# SchemaC.net
KiCad netlist of a schematic drawn in Altium Designer
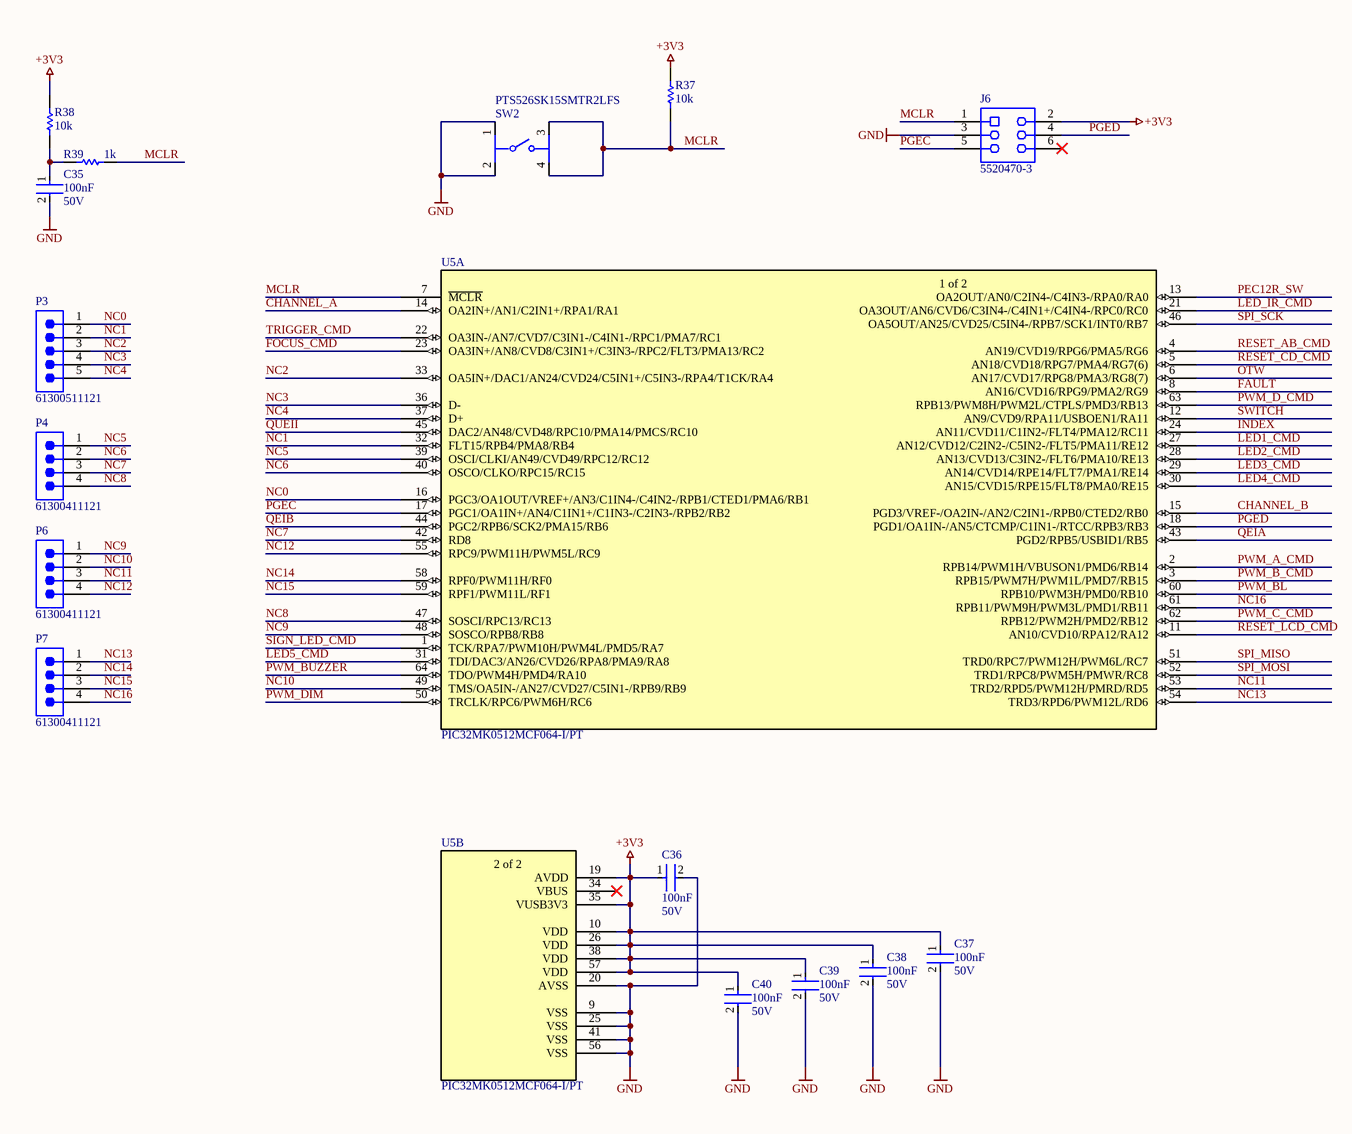
[diagram p0: SchemaC.SchDoc]

(export (version "E")
  (design (tool "Eeschema 10.0.6"))
  (components
    (comp (ref "C35")
      (value "CL21B104KBCNNNC")
      (footprint "FP-CL21-IPC_C")
      (description "CL21 Series 0805 100nF 50V ±10% Tolerance X7R Multilayer Ceramic Chip Capacitor")
      (fields
        (field (name "TOLERANCE") "10%")
        (field (name "CAPACITANCE") "100nF")
        (field (name "VOLTAGE RATING") "50V")
        (field (name "VOLTAGE") "50V")
      )
      (libsource (lib "Altium Content Vault") (part "b4654b650e69147ec39a6b967a45e02"))
    )
    (comp (ref "C36")
      (value "CL21B104KBCNNNC")
      (footprint "FP-CL21-IPC_C")
      (description "CL21 Series 0805 100nF 50V ±10% Tolerance X7R Multilayer Ceramic Chip Capacitor")
      (fields
        (field (name "TOLERANCE") "10%")
        (field (name "CAPACITANCE") "100nF")
        (field (name "VOLTAGE RATING") "50V")
        (field (name "VOLTAGE") "50V")
      )
      (libsource (lib "Altium Content Vault") (part "b4654b650e69147ec39a6b967a45e02"))
    )
    (comp (ref "C37")
      (value "CL21B104KBCNNNC")
      (footprint "FP-CL21-IPC_C")
      (description "CL21 Series 0805 100nF 50V ±10% Tolerance X7R Multilayer Ceramic Chip Capacitor")
      (fields
        (field (name "TOLERANCE") "10%")
        (field (name "CAPACITANCE") "100nF")
        (field (name "VOLTAGE RATING") "50V")
        (field (name "VOLTAGE") "50V")
      )
      (libsource (lib "Altium Content Vault") (part "b4654b650e69147ec39a6b967a45e02"))
    )
    (comp (ref "C38")
      (value "CL21B104KBCNNNC")
      (footprint "FP-CL21-IPC_C")
      (description "CL21 Series 0805 100nF 50V ±10% Tolerance X7R Multilayer Ceramic Chip Capacitor")
      (fields
        (field (name "TOLERANCE") "10%")
        (field (name "CAPACITANCE") "100nF")
        (field (name "VOLTAGE RATING") "50V")
        (field (name "VOLTAGE") "50V")
      )
      (libsource (lib "Altium Content Vault") (part "b4654b650e69147ec39a6b967a45e02"))
    )
    (comp (ref "C39")
      (value "CL21B104KBCNNNC")
      (footprint "FP-CL21-IPC_C")
      (description "CL21 Series 0805 100nF 50V ±10% Tolerance X7R Multilayer Ceramic Chip Capacitor")
      (fields
        (field (name "TOLERANCE") "10%")
        (field (name "CAPACITANCE") "100nF")
        (field (name "VOLTAGE RATING") "50V")
        (field (name "VOLTAGE") "50V")
      )
      (libsource (lib "Altium Content Vault") (part "b4654b650e69147ec39a6b967a45e02"))
    )
    (comp (ref "C40")
      (value "CL21B104KBCNNNC")
      (footprint "FP-CL21-IPC_C")
      (description "CL21 Series 0805 100nF 50V ±10% Tolerance X7R Multilayer Ceramic Chip Capacitor")
      (fields
        (field (name "TOLERANCE") "10%")
        (field (name "CAPACITANCE") "100nF")
        (field (name "VOLTAGE RATING") "50V")
        (field (name "VOLTAGE") "50V")
      )
      (libsource (lib "Altium Content Vault") (part "b4654b650e69147ec39a6b967a45e02"))
    )
    (comp (ref "J6")
      (value "5520470-3")
      (footprint "TECO-5520470-3_V")
      (description "Modular Jack, 6 Position, Right Angle, RoHS, Tray")
      (fields (field (name "MANUFACTURER") "TE Connectivity"))
      (libsource (lib "Altium Content Vault") (part "CN-2S-F-R6"))
    )
    (comp (ref "P3")
      (value "61300511121")
      (footprint "61300511121")
      (libsource (lib "Altium Content Vault") (part "Header_Male_1R_05P"))
    )
    (comp (ref "P4")
      (value "61300411121")
      (footprint "61300411121")
      (libsource (lib "Altium Content Vault") (part "Header_Male_1R_04P"))
    )
    (comp (ref "P6")
      (value "61300411121")
      (footprint "61300411121")
      (libsource (lib "Altium Content Vault") (part "Header_Male_1R_04P"))
    )
    (comp (ref "P7")
      (value "61300411121")
      (footprint "61300411121")
      (libsource (lib "Altium Content Vault") (part "Header_Male_1R_04P"))
    )
    (comp (ref "R37")
      (value "RC0805JR-0710KL")
      (footprint "RESC2013X60X35ML10T20")
      (description "Chip Resistor, 10 KOhm, +/- 5%, 0.125 W, -55 to 155 degC, 0805 (2012 Metric), RoHS, Tape and Reel")
      (fields (field (name "MANUFACTURER") "Yageo") (field (name "RESISTANCE") "10k"))
      (libsource (lib "Altium Content Vault") (part "RES-2"))
    )
    (comp (ref "R38")
      (value "RC0805JR-0710KL")
      (footprint "RESC2013X60X35ML10T20")
      (description "Chip Resistor, 10 KOhm, +/- 5%, 0.125 W, -55 to 155 degC, 0805 (2012 Metric), RoHS, Tape and Reel")
      (fields (field (name "MANUFACTURER") "Yageo") (field (name "RESISTANCE") "10k"))
      (libsource (lib "Altium Content Vault") (part "RES-2"))
    )
    (comp (ref "R39")
      (value "RC0805FR-071KL")
      (footprint "RESC2013X60X35ML10T20")
      (description "Chip Resistor, 1 KOhm, +/- 1%, 125 mW, -55 to 155 degC, 0805 (2012 Metric), RoHS, Tape and Reel")
      (fields
        (field (name "RESISTANCE") "1k")
        (field (name "TOLERANCE") "1%")
        (field (name "MANUFACTURER") "Yageo")
      )
      (libsource (lib "Altium Content Vault") (part "RES-2"))
    )
    (comp (ref "SW2")
      (value "PTS526SK15SMTR2LFS")
      (footprint "FP-PTS526SK15SMTR2LFS-MFG")
      (description "Tactile Switch SPST-NO Top Actuated Surface Mount")
      (fields (field (name "MANUFACTURER") "C&K"))
      (libsource (lib "Altium Content Vault") (part "b8895f3f4cefb76e1819d2863dba89b"))
    )
    (comp (ref "U5")
      (value "PIC32MK0512MCF064-I/PT")
      (footprint "TQFP64_PT_MCH")
      (fields (field (name "COPYRIGHT") "Copyright (C) 2023 Ultra Librarian. All rights reserved."))
      (libsource (lib "SymbLib") (part "PIC32MK0512MCF064-I/PT"))
    )
  )
  (nets
    (net (code "1") (name "+3V3") (class "Default")
      (node (ref "C36") (pin "1") (pinfunction "1_1") (pintype "passive"))
      (node (ref "C37") (pin "1") (pinfunction "1_1") (pintype "passive"))
      (node (ref "C38") (pin "1") (pinfunction "1_1") (pintype "passive"))
      (node (ref "C39") (pin "1") (pinfunction "1_1") (pintype "passive"))
      (node (ref "C40") (pin "1") (pinfunction "1_1") (pintype "passive"))
      (node (ref "J6") (pin "2") (pinfunction "2_2") (pintype "passive"))
      (node (ref "R37") (pin "2") (pinfunction "2_2") (pintype "passive"))
      (node (ref "R38") (pin "2") (pinfunction "2_2") (pintype "passive"))
      (node (ref "U5") (pin "10") (pinfunction "VDD_10") (pintype "power_in"))
      (node (ref "U5") (pin "19") (pinfunction "AVDD_19") (pintype "power_in"))
      (node (ref "U5") (pin "26") (pinfunction "VDD_26") (pintype "power_in"))
      (node (ref "U5") (pin "35") (pinfunction "VUSB3V3_35") (pintype "power_in"))
      (node (ref "U5") (pin "38") (pinfunction "VDD_38") (pintype "power_in"))
      (node (ref "U5") (pin "57") (pinfunction "VDD_57") (pintype "power_in"))
    )
    (net (code "2") (name "/CHANNEL_A") (class "Default")
      (node (ref "U5") (pin "14") (pinfunction "OA2IN+/AN1/C2IN1+/RPA1/RA1_14") (pintype "bidirectional"))
    )
    (net (code "3") (name "/CHANNEL_B") (class "Default")
      (node (ref "U5") (pin "15") (pinfunction "PGD3/VREF-/OA2IN-/AN2/C2IN1-/RPB0/CTED2/RB0_15") (pintype "bidirectional"))
    )
    (net (code "4") (name "/FAULT") (class "Default")
      (node (ref "U5") (pin "8") (pinfunction "AN16/CVD16/RPG9/PMA2/RG9_8") (pintype "bidirectional"))
    )
    (net (code "5") (name "/FOCUS_CMD") (class "Default")
      (node (ref "U5") (pin "23") (pinfunction "OA3IN+/AN8/CVD8/C3IN1+/C3IN3-/RPC2/FLT3/PMA13/RC2_23") (pintype "bidirectional"))
    )
    (net (code "6") (name "/INDEX") (class "Default")
      (node (ref "U5") (pin "24") (pinfunction "AN11/CVD11/C1IN2-/FLT4/PMA12/RC11_24") (pintype "bidirectional"))
    )
    (net (code "7") (name "/LED1_CMD") (class "Default")
      (node (ref "U5") (pin "27") (pinfunction "AN12/CVD12/C2IN2-/C5IN2-/FLT5/PMA11/RE12_27") (pintype "bidirectional"))
    )
    (net (code "8") (name "/LED2_CMD") (class "Default")
      (node (ref "U5") (pin "28") (pinfunction "AN13/CVD13/C3IN2-/FLT6/PMA10/RE13_28") (pintype "bidirectional"))
    )
    (net (code "9") (name "/LED3_CMD") (class "Default")
      (node (ref "U5") (pin "29") (pinfunction "AN14/CVD14/RPE14/FLT7/PMA1/RE14_29") (pintype "bidirectional"))
    )
    (net (code "10") (name "/LED4_CMD") (class "Default")
      (node (ref "U5") (pin "30") (pinfunction "AN15/CVD15/RPE15/FLT8/PMA0/RE15_30") (pintype "bidirectional"))
    )
    (net (code "11") (name "/LED5_CMD") (class "Default")
      (node (ref "U5") (pin "31") (pinfunction "TDI/DAC3/AN26/CVD26/RPA8/PMA9/RA8_31") (pintype "bidirectional"))
    )
    (net (code "12") (name "/LED_IR_CMD") (class "Default")
      (node (ref "U5") (pin "21") (pinfunction "OA3OUT/AN6/CVD6/C3IN4-/C4IN1+/C4IN4-/RPC0/RC0_21") (pintype "bidirectional"))
    )
    (net (code "13") (name "/MCLR") (class "Default")
      (node (ref "J6") (pin "1") (pinfunction "1_1") (pintype "passive"))
      (node (ref "R37") (pin "1") (pinfunction "1_1") (pintype "passive"))
      (node (ref "R39") (pin "2") (pinfunction "2_2") (pintype "passive"))
      (node (ref "SW2") (pin "3") (pinfunction "3_3") (pintype "passive"))
      (node (ref "SW2") (pin "4") (pinfunction "4_4") (pintype "passive"))
      (node (ref "U5") (pin "7") (pinfunction "~{MCLR}_7") (pintype "passive"))
    )
    (net (code "14") (name "/NC0") (class "Default")
      (node (ref "P3") (pin "1") (pinfunction "1_1") (pintype "passive"))
      (node (ref "U5") (pin "16") (pinfunction "PGC3/OA1OUT/VREF+/AN3/C1IN4-/C4IN2-/RPB1/CTED1/PMA6/RB1_16") (pintype "bidirectional"))
    )
    (net (code "15") (name "/NC1") (class "Default")
      (node (ref "P3") (pin "2") (pinfunction "2_2") (pintype "passive"))
      (node (ref "U5") (pin "32") (pinfunction "FLT15/RPB4/PMA8/RB4_32") (pintype "bidirectional"))
    )
    (net (code "16") (name "/NC2") (class "Default")
      (node (ref "P3") (pin "3") (pinfunction "3_3") (pintype "passive"))
      (node (ref "U5") (pin "33") (pinfunction "OA5IN+/DAC1/AN24/CVD24/C5IN1+/C5IN3-/RPA4/T1CK/RA4_33") (pintype "bidirectional"))
    )
    (net (code "17") (name "/NC3") (class "Default")
      (node (ref "P3") (pin "4") (pinfunction "4_4") (pintype "passive"))
      (node (ref "U5") (pin "36") (pinfunction "D-_36") (pintype "bidirectional"))
    )
    (net (code "18") (name "/NC4") (class "Default")
      (node (ref "P3") (pin "5") (pinfunction "5_5") (pintype "passive"))
      (node (ref "U5") (pin "37") (pinfunction "D+_37") (pintype "bidirectional"))
    )
    (net (code "19") (name "/NC5") (class "Default")
      (node (ref "P4") (pin "1") (pinfunction "1_1") (pintype "passive"))
      (node (ref "U5") (pin "39") (pinfunction "OSCI/CLKI/AN49/CVD49/RPC12/RC12_39") (pintype "bidirectional"))
    )
    (net (code "20") (name "/NC6") (class "Default")
      (node (ref "P4") (pin "2") (pinfunction "2_2") (pintype "passive"))
      (node (ref "U5") (pin "40") (pinfunction "OSCO/CLKO/RPC15/RC15_40") (pintype "bidirectional"))
    )
    (net (code "21") (name "/NC7") (class "Default")
      (node (ref "P4") (pin "3") (pinfunction "3_3") (pintype "passive"))
      (node (ref "U5") (pin "42") (pinfunction "RD8_42") (pintype "bidirectional"))
    )
    (net (code "22") (name "/NC8") (class "Default")
      (node (ref "P4") (pin "4") (pinfunction "4_4") (pintype "passive"))
      (node (ref "U5") (pin "47") (pinfunction "SOSCI/RPC13/RC13_47") (pintype "bidirectional"))
    )
    (net (code "23") (name "/NC9") (class "Default")
      (node (ref "P6") (pin "1") (pinfunction "1_1") (pintype "passive"))
      (node (ref "U5") (pin "48") (pinfunction "SOSCO/RPB8/RB8_48") (pintype "bidirectional"))
    )
    (net (code "24") (name "/NC10") (class "Default")
      (node (ref "P6") (pin "2") (pinfunction "2_2") (pintype "passive"))
      (node (ref "U5") (pin "49") (pinfunction "TMS/OA5IN-/AN27/CVD27/C5IN1-/RPB9/RB9_49") (pintype "bidirectional"))
    )
    (net (code "25") (name "/NC11") (class "Default")
      (node (ref "P6") (pin "3") (pinfunction "3_3") (pintype "passive"))
      (node (ref "U5") (pin "53") (pinfunction "TRD2/RPD5/PWM12H/PMRD/RD5_53") (pintype "bidirectional"))
    )
    (net (code "26") (name "/NC12") (class "Default")
      (node (ref "P6") (pin "4") (pinfunction "4_4") (pintype "passive"))
      (node (ref "U5") (pin "55") (pinfunction "RPC9/PWM11H/PWM5L/RC9_55") (pintype "bidirectional"))
    )
    (net (code "27") (name "/NC13") (class "Default")
      (node (ref "P7") (pin "1") (pinfunction "1_1") (pintype "passive"))
      (node (ref "U5") (pin "54") (pinfunction "TRD3/RPD6/PWM12L/RD6_54") (pintype "bidirectional"))
    )
    (net (code "28") (name "/NC14") (class "Default")
      (node (ref "P7") (pin "2") (pinfunction "2_2") (pintype "passive"))
      (node (ref "U5") (pin "58") (pinfunction "RPF0/PWM11H/RF0_58") (pintype "bidirectional"))
    )
    (net (code "29") (name "/NC15") (class "Default")
      (node (ref "P7") (pin "3") (pinfunction "3_3") (pintype "passive"))
      (node (ref "U5") (pin "59") (pinfunction "RPF1/PWM11L/RF1_59") (pintype "bidirectional"))
    )
    (net (code "30") (name "/NC16") (class "Default")
      (node (ref "P7") (pin "4") (pinfunction "4_4") (pintype "passive"))
      (node (ref "U5") (pin "61") (pinfunction "RPB11/PWM9H/PWM3L/PMD1/RB11_61") (pintype "bidirectional"))
    )
    (net (code "31") (name "/OTW") (class "Default")
      (node (ref "U5") (pin "6") (pinfunction "AN17/CVD17/RPG8/PMA3/RG8(7)_6") (pintype "bidirectional"))
    )
    (net (code "32") (name "/PEC12R_SW") (class "Default")
      (node (ref "U5") (pin "13") (pinfunction "OA2OUT/AN0/C2IN4-/C4IN3-/RPA0/RA0_13") (pintype "bidirectional"))
    )
    (net (code "33") (name "/PGEC") (class "Default")
      (node (ref "J6") (pin "5") (pinfunction "5_5") (pintype "passive"))
      (node (ref "U5") (pin "17") (pinfunction "PGC1/OA1IN+/AN4/C1IN1+/C1IN3-/C2IN3-/RPB2/RB2_17") (pintype "bidirectional"))
    )
    (net (code "34") (name "/PGED") (class "Default")
      (node (ref "J6") (pin "4") (pinfunction "4_4") (pintype "passive"))
      (node (ref "U5") (pin "18") (pinfunction "PGD1/OA1IN-/AN5/CTCMP/C1IN1-/RTCC/RPB3/RB3_18") (pintype "bidirectional"))
    )
    (net (code "35") (name "/PWM_A_CMD") (class "Default")
      (node (ref "U5") (pin "2") (pinfunction "RPB14/PWM1H/VBUSON1/PMD6/RB14_2") (pintype "bidirectional"))
    )
    (net (code "36") (name "/PWM_BL") (class "Default")
      (node (ref "U5") (pin "60") (pinfunction "RPB10/PWM3H/PMD0/RB10_60") (pintype "bidirectional"))
    )
    (net (code "37") (name "/PWM_BUZZER") (class "Default")
      (node (ref "U5") (pin "64") (pinfunction "TDO/PWM4H/PMD4/RA10_64") (pintype "bidirectional"))
    )
    (net (code "38") (name "/PWM_B_CMD") (class "Default")
      (node (ref "U5") (pin "3") (pinfunction "RPB15/PWM7H/PWM1L/PMD7/RB15_3") (pintype "bidirectional"))
    )
    (net (code "39") (name "/PWM_C_CMD") (class "Default")
      (node (ref "U5") (pin "62") (pinfunction "RPB12/PWM2H/PMD2/RB12_62") (pintype "bidirectional"))
    )
    (net (code "40") (name "/PWM_DIM") (class "Default")
      (node (ref "U5") (pin "50") (pinfunction "TRCLK/RPC6/PWM6H/RC6_50") (pintype "bidirectional"))
    )
    (net (code "41") (name "/PWM_D_CMD") (class "Default")
      (node (ref "U5") (pin "63") (pinfunction "RPB13/PWM8H/PWM2L/CTPLS/PMD3/RB13_63") (pintype "bidirectional"))
    )
    (net (code "42") (name "/QEIA") (class "Default")
      (node (ref "U5") (pin "43") (pinfunction "PGD2/RPB5/USBID1/RB5_43") (pintype "bidirectional"))
    )
    (net (code "43") (name "/QEIB") (class "Default")
      (node (ref "U5") (pin "44") (pinfunction "PGC2/RPB6/SCK2/PMA15/RB6_44") (pintype "bidirectional"))
    )
    (net (code "44") (name "/QUEII") (class "Default")
      (node (ref "U5") (pin "45") (pinfunction "DAC2/AN48/CVD48/RPC10/PMA14/PMCS/RC10_45") (pintype "bidirectional"))
    )
    (net (code "45") (name "/RESET_AB_CMD") (class "Default")
      (node (ref "U5") (pin "4") (pinfunction "AN19/CVD19/RPG6/PMA5/RG6_4") (pintype "bidirectional"))
    )
    (net (code "46") (name "/RESET_CD_CMD") (class "Default")
      (node (ref "U5") (pin "5") (pinfunction "AN18/CVD18/RPG7/PMA4/RG7(6)_5") (pintype "bidirectional"))
    )
    (net (code "47") (name "/RESET_LCD_CMD") (class "Default")
      (node (ref "U5") (pin "11") (pinfunction "AN10/CVD10/RPA12/RA12_11") (pintype "bidirectional"))
    )
    (net (code "48") (name "/SIGN_LED_CMD") (class "Default")
      (node (ref "U5") (pin "1") (pinfunction "TCK/RPA7/PWM10H/PWM4L/PMD5/RA7_1") (pintype "bidirectional"))
    )
    (net (code "49") (name "/SPI_MISO") (class "Default")
      (node (ref "U5") (pin "51") (pinfunction "TRD0/RPC7/PWM12H/PWM6L/RC7_51") (pintype "bidirectional"))
    )
    (net (code "50") (name "/SPI_MOSI") (class "Default")
      (node (ref "U5") (pin "52") (pinfunction "TRD1/RPC8/PWM5H/PMWR/RC8_52") (pintype "bidirectional"))
    )
    (net (code "51") (name "/SPI_SCK") (class "Default")
      (node (ref "U5") (pin "46") (pinfunction "OA5OUT/AN25/CVD25/C5IN4-/RPB7/SCK1/INT0/RB7_46") (pintype "bidirectional"))
    )
    (net (code "52") (name "/SWITCH") (class "Default")
      (node (ref "U5") (pin "12") (pinfunction "AN9/CVD9/RPA11/USBOEN1/RA11_12") (pintype "bidirectional"))
    )
    (net (code "53") (name "/TRIGGER_CMD") (class "Default")
      (node (ref "U5") (pin "22") (pinfunction "OA3IN-/AN7/CVD7/C3IN1-/C4IN1-/RPC1/PMA7/RC1_22") (pintype "bidirectional"))
    )
    (net (code "54") (name "GND") (class "Default")
      (node (ref "C35") (pin "2") (pinfunction "2_2") (pintype "passive"))
      (node (ref "C36") (pin "2") (pinfunction "2_2") (pintype "passive"))
      (node (ref "C37") (pin "2") (pinfunction "2_2") (pintype "passive"))
      (node (ref "C38") (pin "2") (pinfunction "2_2") (pintype "passive"))
      (node (ref "C39") (pin "2") (pinfunction "2_2") (pintype "passive"))
      (node (ref "C40") (pin "2") (pinfunction "2_2") (pintype "passive"))
      (node (ref "J6") (pin "3") (pinfunction "3_3") (pintype "passive"))
      (node (ref "SW2") (pin "1") (pinfunction "1_1") (pintype "passive"))
      (node (ref "SW2") (pin "2") (pinfunction "2_2") (pintype "passive"))
      (node (ref "U5") (pin "20") (pinfunction "AVSS_20") (pintype "passive"))
      (node (ref "U5") (pin "25") (pinfunction "VSS_25") (pintype "passive"))
      (node (ref "U5") (pin "41") (pinfunction "VSS_41") (pintype "passive"))
      (node (ref "U5") (pin "56") (pinfunction "VSS_56") (pintype "passive"))
      (node (ref "U5") (pin "9") (pinfunction "VSS_9") (pintype "passive"))
    )
    (net (code "55") (name "Net-(C35-Pad1)") (class "Default")
      (node (ref "C35") (pin "1") (pinfunction "1_1") (pintype "passive"))
      (node (ref "R38") (pin "1") (pinfunction "1_1") (pintype "passive"))
      (node (ref "R39") (pin "1") (pinfunction "1_1") (pintype "passive"))
    )
    (net (code "56") (name "unconnected-(J6-Pad6)") (class "Default")
      (node (ref "J6") (pin "6") (pinfunction "6_6") (pintype "passive+no_connect"))
    )
    (net (code "57") (name "unconnected-(U5B-VBUS-Pad34)") (class "Default")
      (node (ref "U5") (pin "34") (pinfunction "VBUS_34") (pintype "power_in+no_connect"))
    )
  )
)
